# ATtiny_4585_dev_board_with_power_reg_and.net
KiCad netlist of a schematic drawn in EAGLE
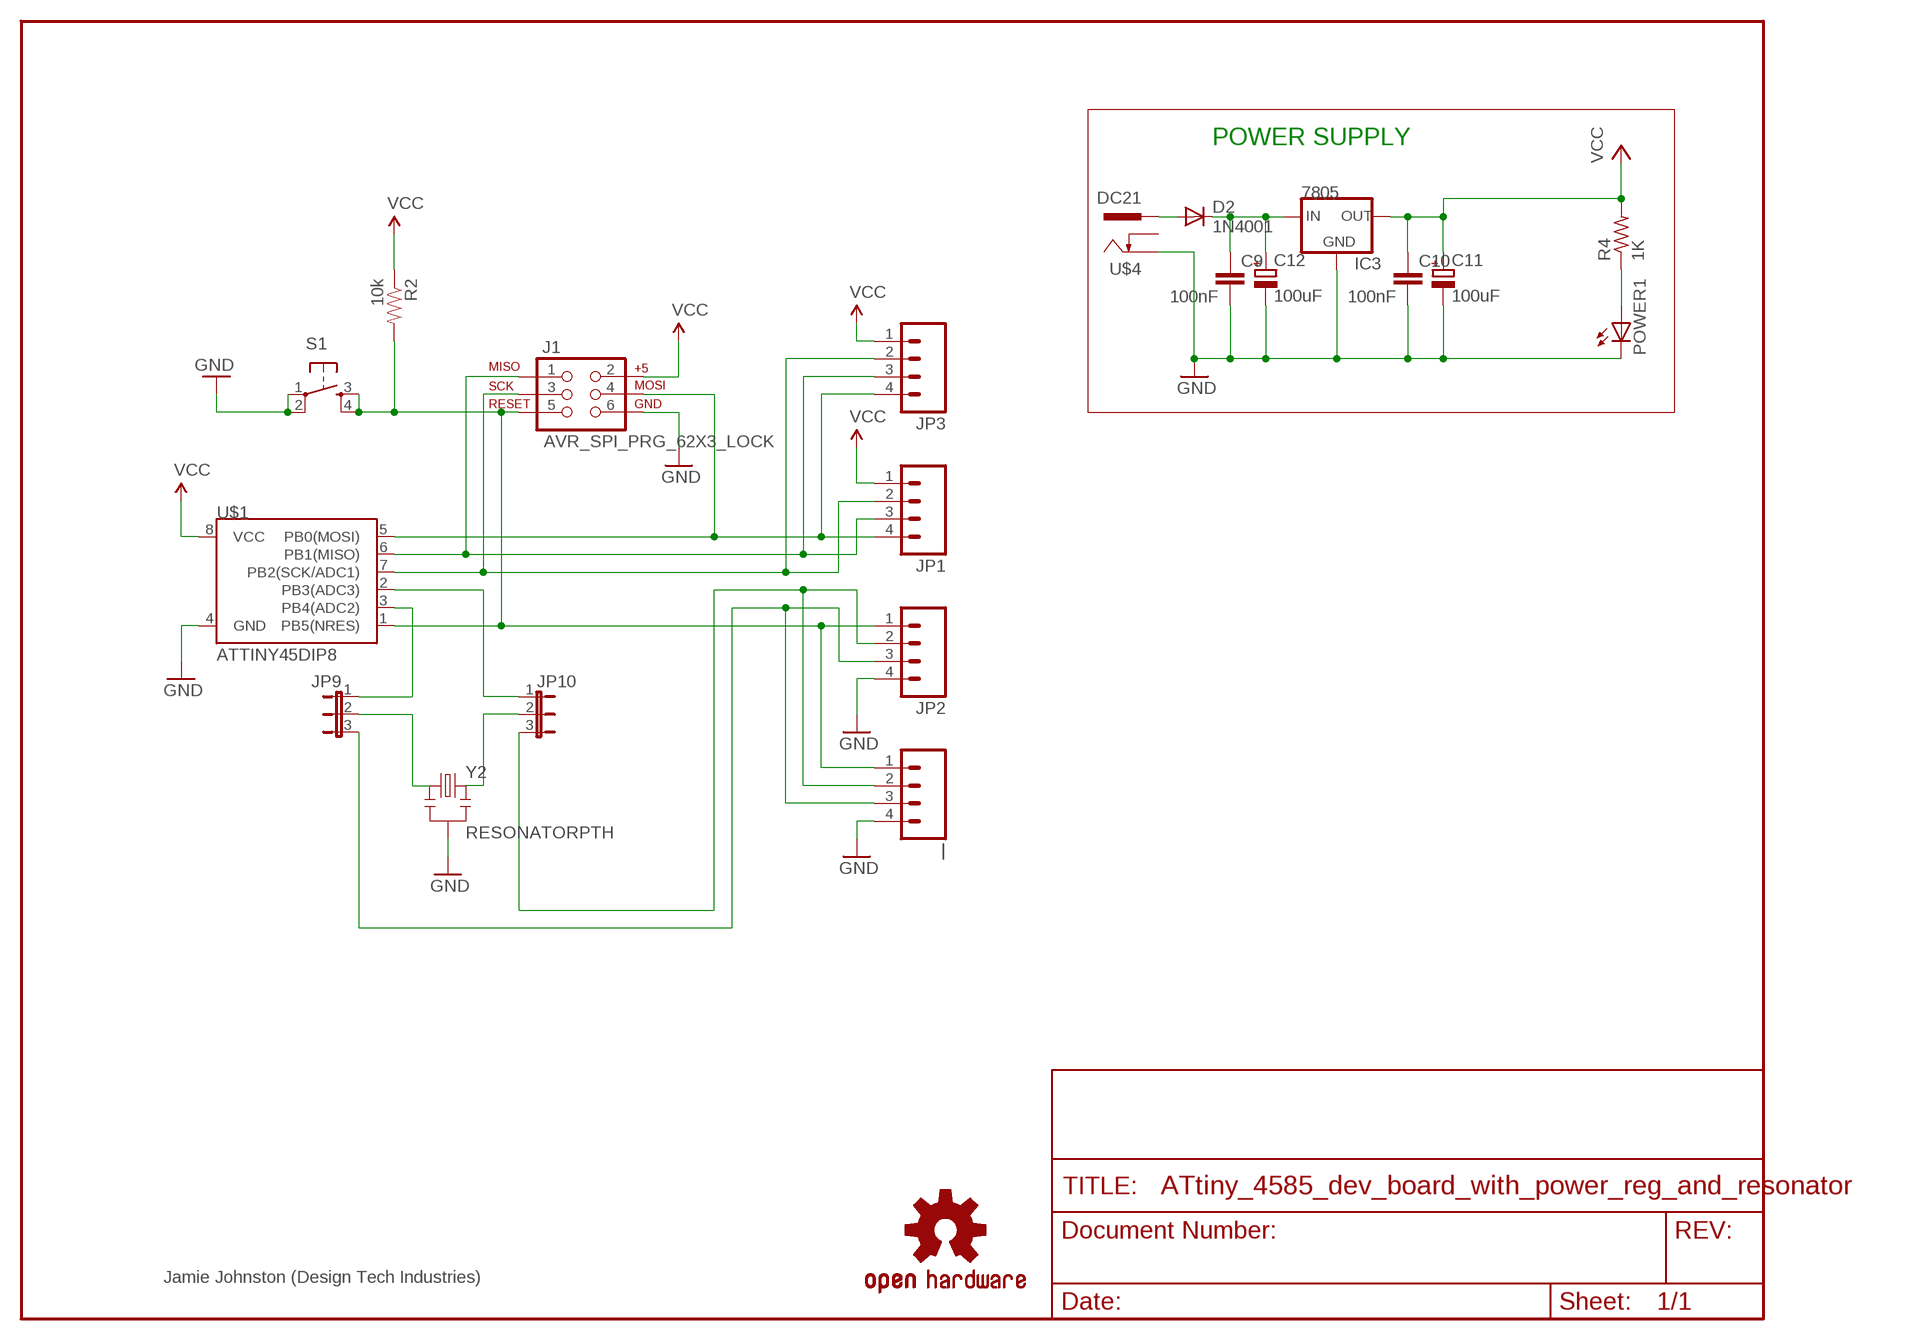
[diagram p0: schematic, sheet 1]

(export (version "E")
  (design (tool "Eeschema 10.0.6"))
  (components
    (comp (ref "C9")
      (value "100nF")
      (footprint "eagle-import:C050-030X075")
      (libsource (lib "eagle-import") (part "C-EU050-030X075"))
    )
    (comp (ref "C10")
      (value "100nF")
      (footprint "eagle-import:C050-030X075")
      (libsource (lib "eagle-import") (part "C-EU050-030X075"))
    )
    (comp (ref "C11")
      (value "100uF")
      (footprint "eagle-import:E2,5-6")
      (libsource (lib "eagle-import") (part "CPOL-EUE2.5-6"))
    )
    (comp (ref "C12")
      (value "100uF")
      (footprint "eagle-import:E2,5-6")
      (libsource (lib "eagle-import") (part "CPOL-EUE2.5-6"))
    )
    (comp (ref "D2")
      (value "1N4001")
      (footprint "eagle-import:DO41-10")
      (libsource (lib "eagle-import") (part "1N4004"))
    )
    (comp (ref "IC3")
      (value "7805")
      (footprint "eagle-import:TO220-IGO")
      (libsource (lib "eagle-import") (part "V_REG_78XXSINK"))
    )
    (comp (ref "J1")
      (value "AVR_SPI_PRG_62X3_LOCK")
      (footprint "eagle-import:2X3_LOCK")
      (libsource (lib "eagle-import") (part "AVR_SPI_PRG_62X3_LOCK"))
    )
    (comp (ref "JP1")
      (value "M04LOCK")
      (footprint "eagle-import:1X04_LOCK")
      (libsource (lib "eagle-import") (part "M04LOCK"))
    )
    (comp (ref "JP2")
      (value "M04LOCK")
      (footprint "eagle-import:1X04_LOCK")
      (libsource (lib "eagle-import") (part "M04LOCK"))
    )
    (comp (ref "JP3")
      (value "M04LOCK")
      (footprint "eagle-import:1X04_LOCK")
      (libsource (lib "eagle-import") (part "M04LOCK"))
    )
    (comp (ref "JP9")
      (value "JP2E")
      (footprint "eagle-import:JP2")
      (libsource (lib "eagle-import") (part "JP2E"))
    )
    (comp (ref "JP10")
      (value "JP2E")
      (footprint "eagle-import:JP2")
      (libsource (lib "eagle-import") (part "JP2E"))
    )
    (comp (ref "POWER1")
      (value "LED3MM")
      (footprint "eagle-import:LED3MM")
      (libsource (lib "eagle-import") (part "LED3MM"))
    )
    (comp (ref "R2")
      (value "10k")
      (footprint "eagle-import:AXIAL-0.4")
      (libsource (lib "eagle-import") (part "RESISTORPTH-1/4W"))
    )
    (comp (ref "R4")
      (value "1K")
      (footprint "eagle-import:0207_2V")
      (libsource (lib "eagle-import") (part "R-US_0207/2V"))
    )
    (comp (ref "S1")
      (value "TAC_SWITCHPTH")
      (footprint "eagle-import:TACTILE-PTH")
      (libsource (lib "eagle-import") (part "TAC_SWITCHPTH"))
    )
    (comp (ref "U$1")
      (value "ATTINY45DIP8")
      (footprint "eagle-import:DIP08")
      (libsource (lib "eagle-import") (part "ATTINY45DIP8"))
    )
    (comp (ref "U$3")
      (value "OSHW-LOGOM")
      (footprint "eagle-import:OSHW-LOGO-M")
      (libsource (lib "eagle-import") (part "OSHW-LOGOM"))
    )
    (comp (ref "U$4")
      (value "DC21")
      (footprint "eagle-import:DCSKT")
      (libsource (lib "eagle-import") (part "DC21"))
    )
    (comp (ref "Y2")
      (value "RESONATORPTH")
      (footprint "eagle-import:RESONATOR-PTH")
      (libsource (lib "eagle-import") (part "RESONATORPTH"))
    )
    (comp (ref "|")
      (value "M04LOCK")
      (footprint "eagle-import:1X04_LOCK")
      (libsource (lib "eagle-import") (part "M04LOCK"))
    )
  )
  (nets
    (net (code "1") (name "GND") (class "Default")
      (node (ref "C10") (pin "2") (pinfunction "2_2") (pintype "passive"))
      (node (ref "C11") (pin "-") (pinfunction "-_-") (pintype "passive"))
      (node (ref "C12") (pin "-") (pinfunction "-_-") (pintype "passive"))
      (node (ref "C9") (pin "2") (pinfunction "2_2") (pintype "passive"))
      (node (ref "IC3") (pin "GND") (pinfunction "GND_GND") (pintype "input"))
      (node (ref "J1") (pin "6") (pinfunction "6_6") (pintype "passive"))
      (node (ref "JP2") (pin "4") (pinfunction "4_4") (pintype "passive"))
      (node (ref "POWER1") (pin "K") (pinfunction "C_K") (pintype "passive"))
      (node (ref "S1") (pin "1") (pinfunction "1_1") (pintype "passive"))
      (node (ref "S1") (pin "2") (pinfunction "2_2") (pintype "passive"))
      (node (ref "U$1") (pin "4") (pinfunction "GND_4") (pintype "bidirectional"))
      (node (ref "U$4") (pin "2") (pinfunction "2_2") (pintype "passive"))
      (node (ref "Y2") (pin "2") (pinfunction "2_2") (pintype "passive"))
      (node (ref "|") (pin "4") (pinfunction "4_4") (pintype "passive"))
    )
    (net (code "2") (name "Net-(C12-Pad+)") (class "Default")
      (node (ref "C12") (pin "+") (pinfunction "+_+") (pintype "passive"))
      (node (ref "C9") (pin "1") (pinfunction "1_1") (pintype "passive"))
      (node (ref "D2") (pin "C") (pinfunction "C_C") (pintype "passive"))
      (node (ref "IC3") (pin "IN") (pinfunction "IN_IN") (pintype "input"))
    )
    (net (code "3") (name "Net-(D2-PadA)") (class "Default")
      (node (ref "D2") (pin "A") (pinfunction "A_A") (pintype "passive"))
      (node (ref "U$4") (pin "1") (pinfunction "1_1") (pintype "passive"))
    )
    (net (code "4") (name "Net-(JP2-Pad3)") (class "Default")
      (node (ref "JP2") (pin "3") (pinfunction "3_3") (pintype "passive"))
      (node (ref "JP9") (pin "3") (pinfunction "3_3") (pintype "passive"))
      (node (ref "|") (pin "3") (pinfunction "3_3") (pintype "passive"))
    )
    (net (code "5") (name "Net-(JP9-Pad2)") (class "Default")
      (node (ref "JP9") (pin "2") (pinfunction "2_2") (pintype "passive"))
      (node (ref "Y2") (pin "1") (pinfunction "1_1") (pintype "passive"))
    )
    (net (code "6") (name "Net-(JP10-Pad2)") (class "Default")
      (node (ref "JP10") (pin "2") (pinfunction "2_2") (pintype "passive"))
      (node (ref "Y2") (pin "3") (pinfunction "3_3") (pintype "passive"))
    )
    (net (code "7") (name "Net-(JP10-Pad3)") (class "Default")
      (node (ref "JP10") (pin "3") (pinfunction "3_3") (pintype "passive"))
      (node (ref "JP2") (pin "2") (pinfunction "2_2") (pintype "passive"))
      (node (ref "|") (pin "2") (pinfunction "2_2") (pintype "passive"))
    )
    (net (code "8") (name "Net-(POWER1-PadA)") (class "Default")
      (node (ref "POWER1") (pin "A") (pinfunction "A_A") (pintype "passive"))
      (node (ref "R4") (pin "1") (pinfunction "1_1") (pintype "passive"))
    )
    (net (code "9") (name "Net-(R2-2)") (class "Default")
      (node (ref "J1") (pin "5") (pinfunction "5_5") (pintype "passive"))
      (node (ref "JP2") (pin "1") (pinfunction "1_1") (pintype "passive"))
      (node (ref "R2") (pin "P$2") (pinfunction "2_P$2") (pintype "passive"))
      (node (ref "S1") (pin "3") (pinfunction "3_3") (pintype "passive"))
      (node (ref "S1") (pin "4") (pinfunction "4_4") (pintype "passive"))
      (node (ref "U$1") (pin "1") (pinfunction "PB5(NRES)_1") (pintype "bidirectional"))
      (node (ref "|") (pin "1") (pinfunction "1_1") (pintype "passive"))
    )
    (net (code "10") (name "Net-(U$1-PB0(MOSI))") (class "Default")
      (node (ref "J1") (pin "4") (pinfunction "4_4") (pintype "passive"))
      (node (ref "JP1") (pin "4") (pinfunction "4_4") (pintype "passive"))
      (node (ref "JP3") (pin "4") (pinfunction "4_4") (pintype "passive"))
      (node (ref "U$1") (pin "5") (pinfunction "PB0(MOSI)_5") (pintype "bidirectional"))
    )
    (net (code "11") (name "Net-(U$1-PB1(MISO))") (class "Default")
      (node (ref "J1") (pin "1") (pinfunction "1_1") (pintype "passive"))
      (node (ref "JP1") (pin "3") (pinfunction "3_3") (pintype "passive"))
      (node (ref "JP3") (pin "3") (pinfunction "3_3") (pintype "passive"))
      (node (ref "U$1") (pin "6") (pinfunction "PB1(MISO)_6") (pintype "bidirectional"))
    )
    (net (code "12") (name "Net-(U$1-PB2(SCK{slash}ADC1))") (class "Default")
      (node (ref "J1") (pin "3") (pinfunction "3_3") (pintype "passive"))
      (node (ref "JP1") (pin "2") (pinfunction "2_2") (pintype "passive"))
      (node (ref "JP3") (pin "2") (pinfunction "2_2") (pintype "passive"))
      (node (ref "U$1") (pin "7") (pinfunction "PB2(SCK/ADC1)_7") (pintype "bidirectional"))
    )
    (net (code "13") (name "Net-(U$1-PB3(ADC3))") (class "Default")
      (node (ref "JP10") (pin "1") (pinfunction "1_1") (pintype "passive"))
      (node (ref "U$1") (pin "2") (pinfunction "PB3(ADC3)_2") (pintype "bidirectional"))
    )
    (net (code "14") (name "Net-(U$1-PB4(ADC2))") (class "Default")
      (node (ref "JP9") (pin "1") (pinfunction "1_1") (pintype "passive"))
      (node (ref "U$1") (pin "3") (pinfunction "PB4(ADC2)_3") (pintype "bidirectional"))
    )
    (net (code "15") (name "VCC") (class "Default")
      (node (ref "C10") (pin "1") (pinfunction "1_1") (pintype "passive"))
      (node (ref "C11") (pin "+") (pinfunction "+_+") (pintype "passive"))
      (node (ref "IC3") (pin "OUT") (pinfunction "OUT_OUT") (pintype "output"))
      (node (ref "J1") (pin "2") (pinfunction "2_2") (pintype "passive"))
      (node (ref "JP1") (pin "1") (pinfunction "1_1") (pintype "passive"))
      (node (ref "JP3") (pin "1") (pinfunction "1_1") (pintype "passive"))
      (node (ref "R2") (pin "P$1") (pinfunction "1_P$1") (pintype "passive"))
      (node (ref "R4") (pin "2") (pinfunction "2_2") (pintype "passive"))
      (node (ref "U$1") (pin "8") (pinfunction "VCC_8") (pintype "bidirectional"))
    )
    (net (code "16") (name "unconnected-(U$4-Pad3)") (class "Default")
      (node (ref "U$4") (pin "3") (pinfunction "3_3") (pintype "passive"))
    )
  )
)
